# 1-Schematic_MatrixBoard.net
KiCad netlist of a schematic drawn in EasyEDA
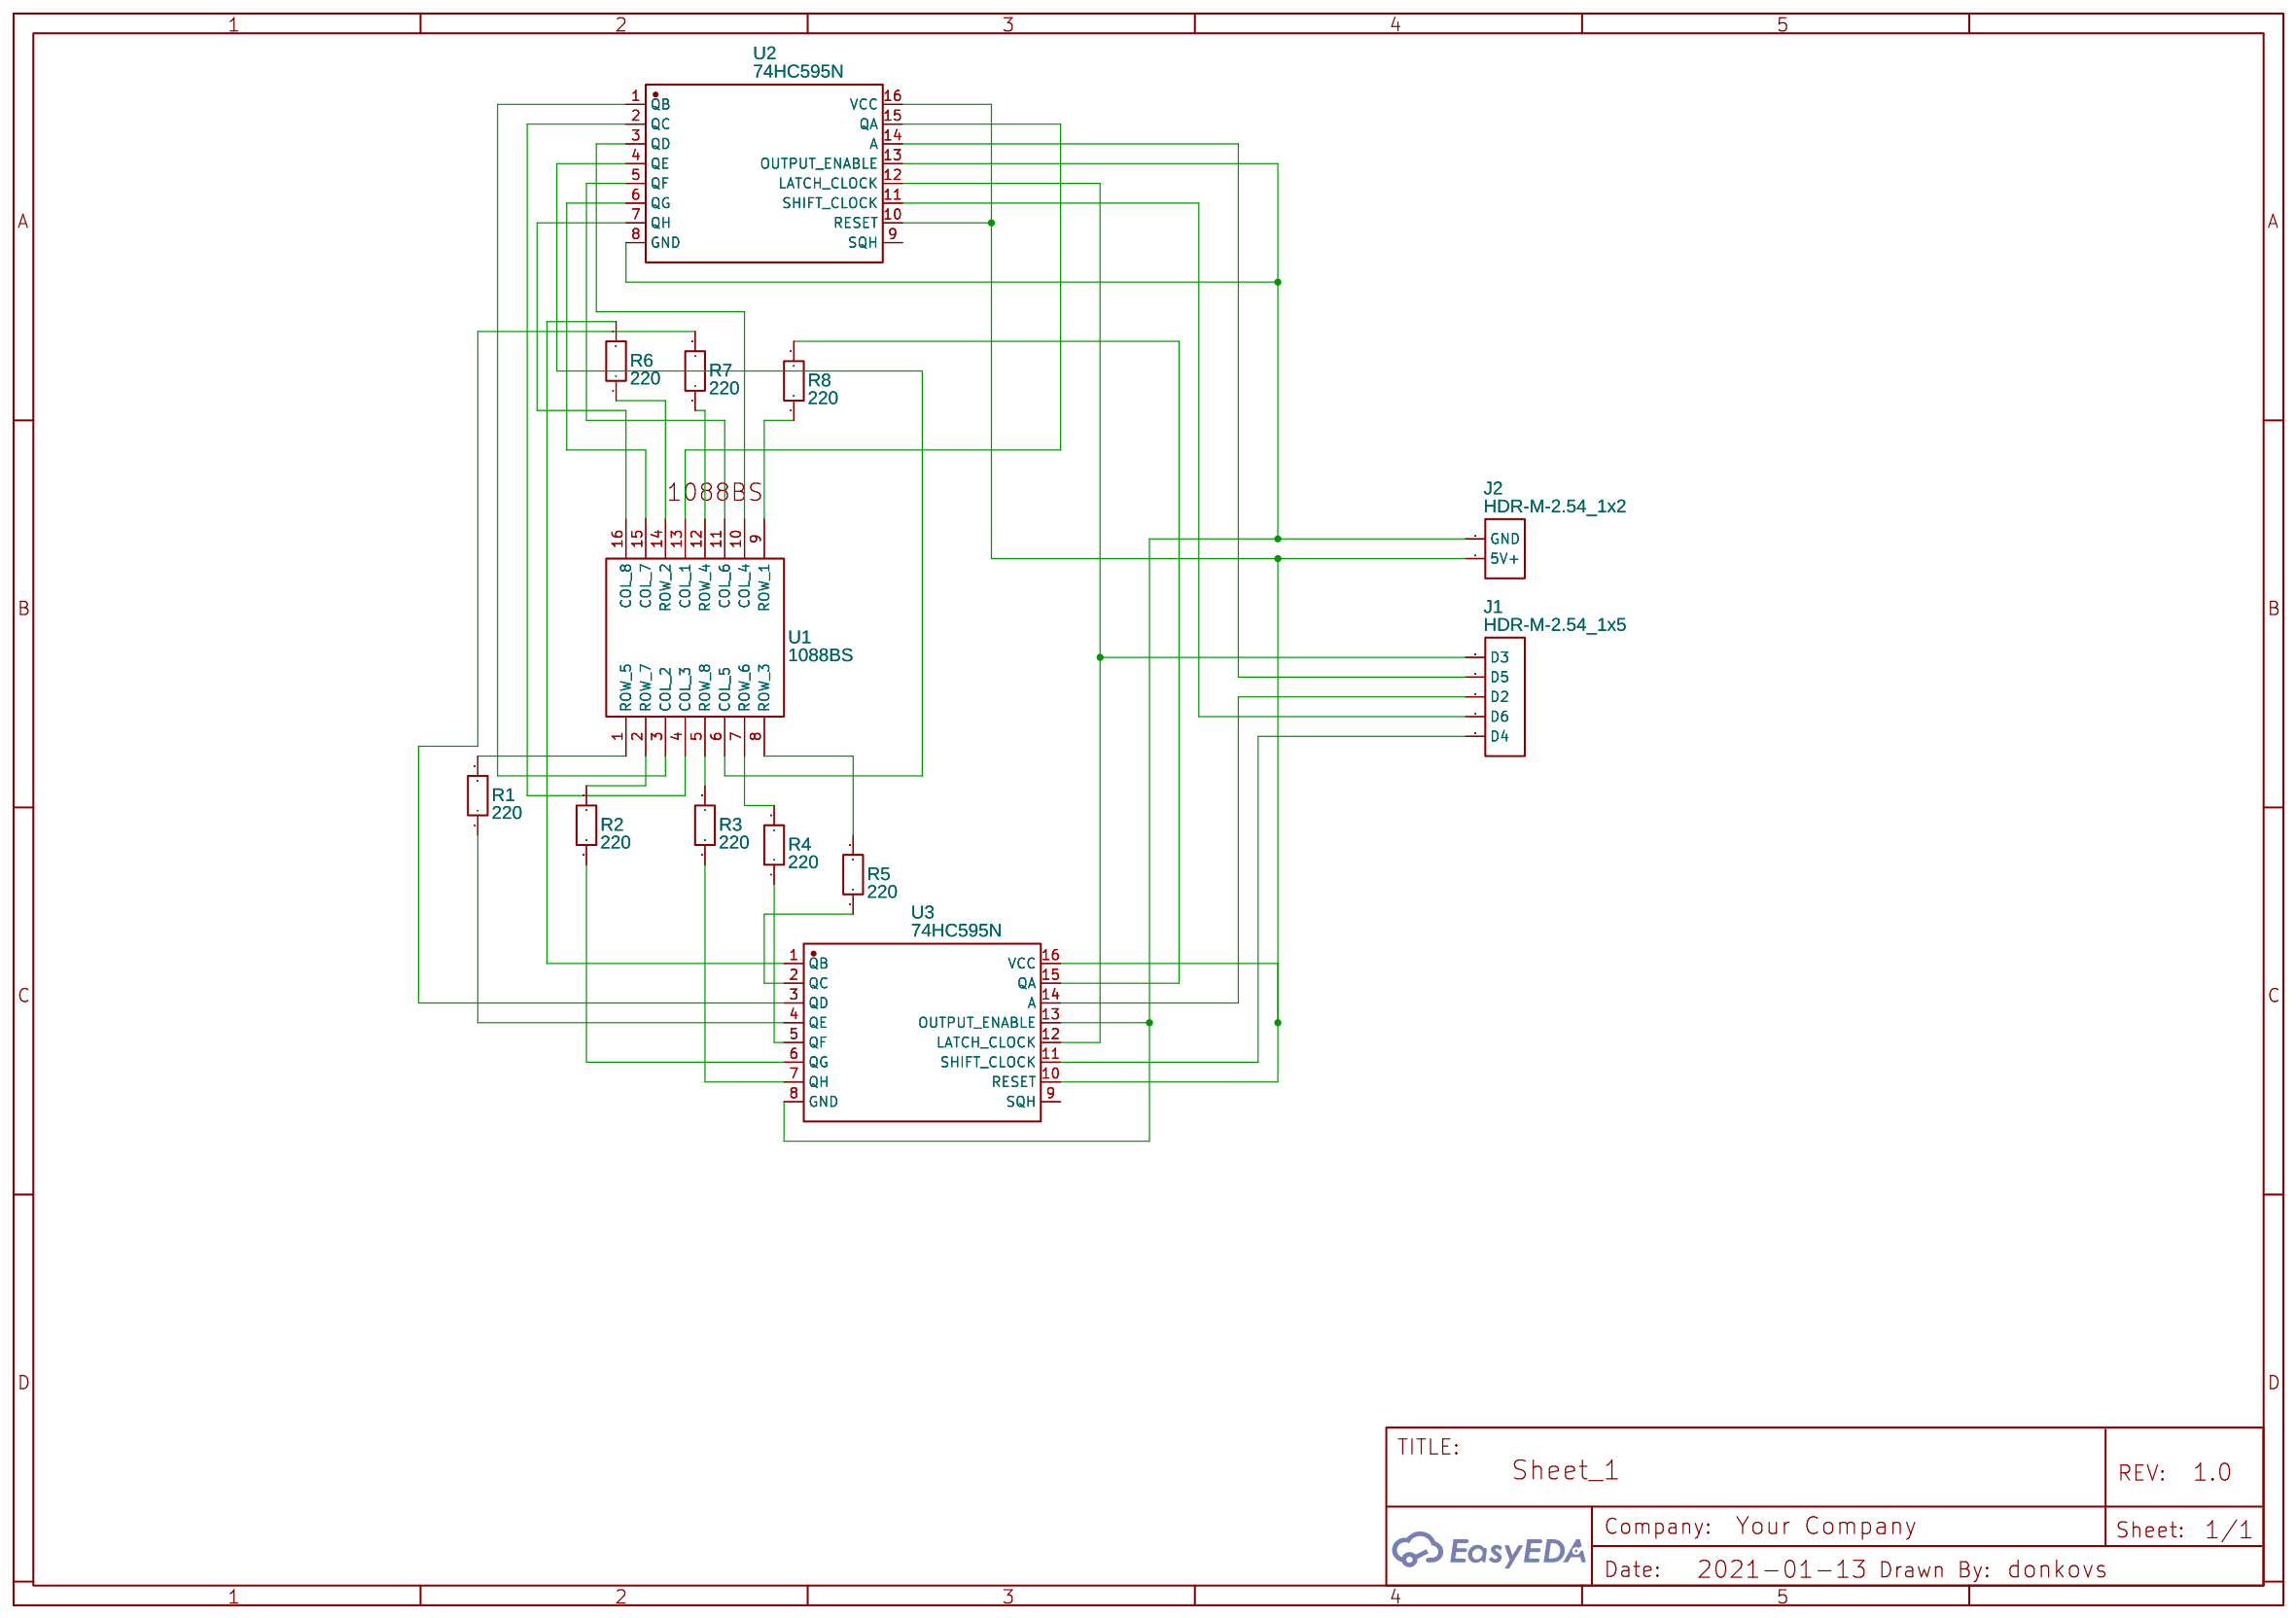
[diagram p0: schematic sheet]

(export (version "E")
  (design (tool "Eeschema 10.0.6"))
  (components
    (comp (ref "J1")
      (value "HDR-M-2.54_1x5")
      (fields (field (name "BOM_Supplier Part") "C358687"))
      (libsource (lib "") (part "HDR-M-2.54_1x5"))
    )
    (comp (ref "J2")
      (value "HDR-M-2.54_1x2")
      (fields (field (name "BOM_Supplier Part") "C124375"))
      (libsource (lib "") (part "HDR-M-2.54_1x2"))
    )
    (comp (ref "R1") (value "220") (libsource (lib "") (part "R_0603_EU")))
    (comp (ref "R2") (value "220") (libsource (lib "") (part "R_0603_EU")))
    (comp (ref "R3") (value "220") (libsource (lib "") (part "R_0603_EU")))
    (comp (ref "R4") (value "220") (libsource (lib "") (part "R_0603_EU")))
    (comp (ref "R5") (value "220") (libsource (lib "") (part "R_0603_EU")))
    (comp (ref "R6") (value "220") (libsource (lib "") (part "R_0603_EU")))
    (comp (ref "R7") (value "220") (libsource (lib "") (part "R_0603_EU")))
    (comp (ref "R8") (value "220") (libsource (lib "") (part "R_0603_EU")))
    (comp (ref "U1") (value "1088BS") (libsource (lib "") (part "1088BS")))
    (comp (ref "U2")
      (value "74HC595N")
      (fields (field (name "BOM_Supplier Part") "C507175"))
      (libsource (lib "") (part "74HC595N"))
    )
    (comp (ref "U3")
      (value "74HC595N")
      (fields (field (name "BOM_Supplier Part") "C507175"))
      (libsource (lib "") (part "74HC595N"))
    )
  )
  (nets
    (net (code "1") (name "Net-(J1-D2)") (class "Default")
      (node (ref "J1") (pin "3") (pinfunction "D2_3") (pintype "unspecified"))
      (node (ref "U3") (pin "14") (pinfunction "A_14") (pintype "unspecified"))
    )
    (net (code "2") (name "Net-(J1-D3)") (class "Default")
      (node (ref "J1") (pin "1") (pinfunction "D3_1") (pintype "unspecified"))
      (node (ref "U2") (pin "12") (pinfunction "LATCH_CLOCK_12") (pintype "unspecified"))
      (node (ref "U3") (pin "12") (pinfunction "LATCH_CLOCK_12") (pintype "unspecified"))
    )
    (net (code "3") (name "Net-(J1-D4)") (class "Default")
      (node (ref "J1") (pin "5") (pinfunction "D4_5") (pintype "unspecified"))
      (node (ref "U3") (pin "11") (pinfunction "SHIFT_CLOCK_11") (pintype "unspecified"))
    )
    (net (code "4") (name "Net-(J1-D5)") (class "Default")
      (node (ref "J1") (pin "2") (pinfunction "D5_2") (pintype "unspecified"))
      (node (ref "U2") (pin "14") (pinfunction "A_14") (pintype "unspecified"))
    )
    (net (code "5") (name "Net-(J1-D6)") (class "Default")
      (node (ref "J1") (pin "4") (pinfunction "D6_4") (pintype "unspecified"))
      (node (ref "U2") (pin "11") (pinfunction "SHIFT_CLOCK_11") (pintype "unspecified"))
    )
    (net (code "6") (name "Net-(J2-5V+)") (class "Default")
      (node (ref "J2") (pin "2") (pinfunction "5V+_2") (pintype "unspecified"))
      (node (ref "U2") (pin "10") (pinfunction "RESET_10") (pintype "unspecified"))
      (node (ref "U2") (pin "16") (pinfunction "VCC_16") (pintype "unspecified"))
      (node (ref "U3") (pin "10") (pinfunction "RESET_10") (pintype "unspecified"))
      (node (ref "U3") (pin "16") (pinfunction "VCC_16") (pintype "unspecified"))
    )
    (net (code "7") (name "Net-(J2-GND)") (class "Default")
      (node (ref "J2") (pin "1") (pinfunction "GND_1") (pintype "unspecified"))
      (node (ref "U2") (pin "13") (pinfunction "OUTPUT_ENABLE_13") (pintype "unspecified"))
      (node (ref "U2") (pin "8") (pinfunction "GND_8") (pintype "unspecified"))
      (node (ref "U3") (pin "13") (pinfunction "OUTPUT_ENABLE_13") (pintype "unspecified"))
      (node (ref "U3") (pin "8") (pinfunction "GND_8") (pintype "unspecified"))
    )
    (net (code "8") (name "Net-(U1-COL_1)") (class "Default")
      (node (ref "U1") (pin "13") (pinfunction "COL_1_13") (pintype "unspecified"))
      (node (ref "U2") (pin "15") (pinfunction "QA_15") (pintype "unspecified"))
    )
    (net (code "9") (name "Net-(U1-COL_2)") (class "Default")
      (node (ref "U1") (pin "3") (pinfunction "COL_2_3") (pintype "unspecified"))
      (node (ref "U2") (pin "1") (pinfunction "QB_1") (pintype "unspecified"))
    )
    (net (code "10") (name "Net-(U1-COL_3)") (class "Default")
      (node (ref "U1") (pin "4") (pinfunction "COL_3_4") (pintype "unspecified"))
      (node (ref "U2") (pin "2") (pinfunction "QC_2") (pintype "unspecified"))
    )
    (net (code "11") (name "Net-(U1-COL_4)") (class "Default")
      (node (ref "U1") (pin "10") (pinfunction "COL_4_10") (pintype "unspecified"))
      (node (ref "U2") (pin "3") (pinfunction "QD_3") (pintype "unspecified"))
    )
    (net (code "12") (name "Net-(U1-COL_5)") (class "Default")
      (node (ref "U1") (pin "6") (pinfunction "COL_5_6") (pintype "unspecified"))
      (node (ref "U2") (pin "4") (pinfunction "QE_4") (pintype "unspecified"))
    )
    (net (code "13") (name "Net-(U1-COL_6)") (class "Default")
      (node (ref "U1") (pin "11") (pinfunction "COL_6_11") (pintype "unspecified"))
      (node (ref "U2") (pin "5") (pinfunction "QF_5") (pintype "unspecified"))
    )
    (net (code "14") (name "Net-(U1-COL_7)") (class "Default")
      (node (ref "U1") (pin "15") (pinfunction "COL_7_15") (pintype "unspecified"))
      (node (ref "U2") (pin "6") (pinfunction "QG_6") (pintype "unspecified"))
    )
    (net (code "15") (name "Net-(U1-COL_8)") (class "Default")
      (node (ref "U1") (pin "16") (pinfunction "COL_8_16") (pintype "unspecified"))
      (node (ref "U2") (pin "7") (pinfunction "QH_7") (pintype "unspecified"))
    )
    (net (code "16") (name "Net-(U1-ROW_1)") (class "Default")
      (node (ref "R8") (pin "1") (pinfunction "1_1") (pintype "unspecified"))
      (node (ref "U1") (pin "9") (pinfunction "ROW_1_9") (pintype "unspecified"))
    )
    (net (code "17") (name "Net-(U1-ROW_2)") (class "Default")
      (node (ref "R6") (pin "1") (pinfunction "1_1") (pintype "unspecified"))
      (node (ref "U1") (pin "14") (pinfunction "ROW_2_14") (pintype "unspecified"))
    )
    (net (code "18") (name "Net-(U1-ROW_3)") (class "Default")
      (node (ref "R5") (pin "2") (pinfunction "2_2") (pintype "unspecified"))
      (node (ref "U1") (pin "8") (pinfunction "ROW_3_8") (pintype "unspecified"))
    )
    (net (code "19") (name "Net-(U1-ROW_4)") (class "Default")
      (node (ref "R7") (pin "1") (pinfunction "1_1") (pintype "unspecified"))
      (node (ref "U1") (pin "12") (pinfunction "ROW_4_12") (pintype "unspecified"))
    )
    (net (code "20") (name "Net-(U1-ROW_5)") (class "Default")
      (node (ref "R1") (pin "2") (pinfunction "2_2") (pintype "unspecified"))
      (node (ref "U1") (pin "1") (pinfunction "ROW_5_1") (pintype "unspecified"))
    )
    (net (code "21") (name "Net-(U1-ROW_6)") (class "Default")
      (node (ref "R4") (pin "2") (pinfunction "2_2") (pintype "unspecified"))
      (node (ref "U1") (pin "7") (pinfunction "ROW_6_7") (pintype "unspecified"))
    )
    (net (code "22") (name "Net-(U1-ROW_7)") (class "Default")
      (node (ref "R2") (pin "2") (pinfunction "2_2") (pintype "unspecified"))
      (node (ref "U1") (pin "2") (pinfunction "ROW_7_2") (pintype "unspecified"))
    )
    (net (code "23") (name "Net-(U1-ROW_8)") (class "Default")
      (node (ref "R3") (pin "2") (pinfunction "2_2") (pintype "unspecified"))
      (node (ref "U1") (pin "5") (pinfunction "ROW_8_5") (pintype "unspecified"))
    )
    (net (code "24") (name "Net-(U3-QA)") (class "Default")
      (node (ref "R8") (pin "2") (pinfunction "2_2") (pintype "unspecified"))
      (node (ref "U3") (pin "15") (pinfunction "QA_15") (pintype "unspecified"))
    )
    (net (code "25") (name "Net-(U3-QB)") (class "Default")
      (node (ref "R6") (pin "2") (pinfunction "2_2") (pintype "unspecified"))
      (node (ref "U3") (pin "1") (pinfunction "QB_1") (pintype "unspecified"))
    )
    (net (code "26") (name "Net-(U3-QC)") (class "Default")
      (node (ref "R5") (pin "1") (pinfunction "1_1") (pintype "unspecified"))
      (node (ref "U3") (pin "2") (pinfunction "QC_2") (pintype "unspecified"))
    )
    (net (code "27") (name "Net-(U3-QD)") (class "Default")
      (node (ref "R7") (pin "2") (pinfunction "2_2") (pintype "unspecified"))
      (node (ref "U3") (pin "3") (pinfunction "QD_3") (pintype "unspecified"))
    )
    (net (code "28") (name "Net-(U3-QE)") (class "Default")
      (node (ref "R1") (pin "1") (pinfunction "1_1") (pintype "unspecified"))
      (node (ref "U3") (pin "4") (pinfunction "QE_4") (pintype "unspecified"))
    )
    (net (code "29") (name "Net-(U3-QF)") (class "Default")
      (node (ref "R4") (pin "1") (pinfunction "1_1") (pintype "unspecified"))
      (node (ref "U3") (pin "5") (pinfunction "QF_5") (pintype "unspecified"))
    )
    (net (code "30") (name "Net-(U3-QG)") (class "Default")
      (node (ref "R2") (pin "1") (pinfunction "1_1") (pintype "unspecified"))
      (node (ref "U3") (pin "6") (pinfunction "QG_6") (pintype "unspecified"))
    )
    (net (code "31") (name "Net-(U3-QH)") (class "Default")
      (node (ref "R3") (pin "1") (pinfunction "1_1") (pintype "unspecified"))
      (node (ref "U3") (pin "7") (pinfunction "QH_7") (pintype "unspecified"))
    )
    (net (code "32") (name "unconnected-(U2-SQH-Pad9)") (class "Default")
      (node (ref "U2") (pin "9") (pinfunction "SQH_9") (pintype "unspecified"))
    )
    (net (code "33") (name "unconnected-(U3-SQH-Pad9)") (class "Default")
      (node (ref "U3") (pin "9") (pinfunction "SQH_9") (pintype "unspecified"))
    )
  )
)
